# PZT_Board.net
KiCad netlist of a schematic drawn in Altium Designer
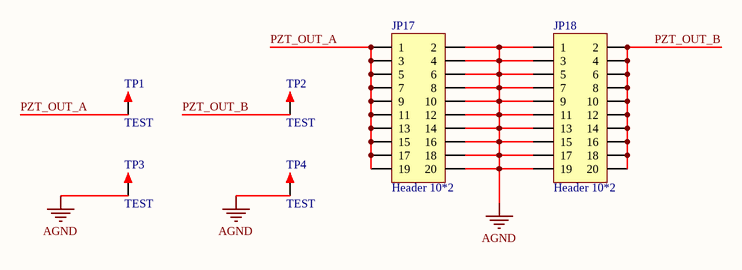
[diagram p0: PZT Board.SchDoc]

(export (version "E")
  (design (tool "Eeschema 10.0.6"))
  (components
    (comp (ref "JP17")
      (value "Header 10*2")
      (footprint "BTB-0.5MM-SMD-M_2*10PIN")
      (description "BTB Connector")
      (libsource (lib "4.6 - BTB连接器") (part "Header 10*2"))
    )
    (comp (ref "JP18")
      (value "Header 10*2")
      (footprint "BTB-0.5MM-SMD-M_2*10PIN")
      (description "BTB Connector")
      (libsource (lib "4.6 - BTB连接器") (part "Header 10*2"))
    )
    (comp (ref "TP1")
      (value "TEST")
      (footprint "TEST 2.0")
      (description "测试点")
      (fields (field (name "版权归属") "封装库来自淘宝 ID：黄晶宝石"))
      (libsource (lib "4.1 - 未分类器件") (part "TEST"))
    )
    (comp (ref "TP2")
      (value "TEST")
      (footprint "TEST 2.0")
      (description "测试点")
      (fields (field (name "版权归属") "封装库来自淘宝 ID：黄晶宝石"))
      (libsource (lib "4.1 - 未分类器件") (part "TEST"))
    )
    (comp (ref "TP3")
      (value "TEST")
      (footprint "TEST 2.0")
      (description "测试点")
      (fields (field (name "版权归属") "封装库来自淘宝 ID：黄晶宝石"))
      (libsource (lib "4.1 - 未分类器件") (part "TEST"))
    )
    (comp (ref "TP4")
      (value "TEST")
      (footprint "TEST 2.0")
      (description "测试点")
      (fields (field (name "版权归属") "封装库来自淘宝 ID：黄晶宝石"))
      (libsource (lib "4.1 - 未分类器件") (part "TEST"))
    )
  )
  (nets
    (net (code "1") (name "/PZT_OUT_A") (class "Default")
      (node (ref "JP17") (pin "1") (pinfunction "1_1") (pintype "passive"))
      (node (ref "JP17") (pin "11") (pinfunction "11_11") (pintype "passive"))
      (node (ref "JP17") (pin "13") (pinfunction "13_13") (pintype "passive"))
      (node (ref "JP17") (pin "15") (pinfunction "15_15") (pintype "passive"))
      (node (ref "JP17") (pin "17") (pinfunction "17_17") (pintype "passive"))
      (node (ref "JP17") (pin "19") (pinfunction "19_19") (pintype "passive"))
      (node (ref "JP17") (pin "3") (pinfunction "3_3") (pintype "passive"))
      (node (ref "JP17") (pin "5") (pinfunction "5_5") (pintype "passive"))
      (node (ref "JP17") (pin "7") (pinfunction "7_7") (pintype "passive"))
      (node (ref "JP17") (pin "9") (pinfunction "9_9") (pintype "passive"))
      (node (ref "TP1") (pin "1") (pinfunction "1_1") (pintype "passive"))
    )
    (net (code "2") (name "/PZT_OUT_B") (class "Default")
      (node (ref "JP18") (pin "10") (pinfunction "10_10") (pintype "passive"))
      (node (ref "JP18") (pin "12") (pinfunction "12_12") (pintype "passive"))
      (node (ref "JP18") (pin "14") (pinfunction "14_14") (pintype "passive"))
      (node (ref "JP18") (pin "16") (pinfunction "16_16") (pintype "passive"))
      (node (ref "JP18") (pin "18") (pinfunction "18_18") (pintype "passive"))
      (node (ref "JP18") (pin "2") (pinfunction "2_2") (pintype "passive"))
      (node (ref "JP18") (pin "20") (pinfunction "20_20") (pintype "passive"))
      (node (ref "JP18") (pin "4") (pinfunction "4_4") (pintype "passive"))
      (node (ref "JP18") (pin "6") (pinfunction "6_6") (pintype "passive"))
      (node (ref "JP18") (pin "8") (pinfunction "8_8") (pintype "passive"))
      (node (ref "TP2") (pin "1") (pinfunction "1_1") (pintype "passive"))
    )
    (net (code "3") (name "AGND") (class "Default")
      (node (ref "JP17") (pin "10") (pinfunction "10_10") (pintype "passive"))
      (node (ref "JP17") (pin "12") (pinfunction "12_12") (pintype "passive"))
      (node (ref "JP17") (pin "14") (pinfunction "14_14") (pintype "passive"))
      (node (ref "JP17") (pin "16") (pinfunction "16_16") (pintype "passive"))
      (node (ref "JP17") (pin "18") (pinfunction "18_18") (pintype "passive"))
      (node (ref "JP17") (pin "2") (pinfunction "2_2") (pintype "passive"))
      (node (ref "JP17") (pin "20") (pinfunction "20_20") (pintype "passive"))
      (node (ref "JP17") (pin "4") (pinfunction "4_4") (pintype "passive"))
      (node (ref "JP17") (pin "6") (pinfunction "6_6") (pintype "passive"))
      (node (ref "JP17") (pin "8") (pinfunction "8_8") (pintype "passive"))
      (node (ref "JP18") (pin "1") (pinfunction "1_1") (pintype "passive"))
      (node (ref "JP18") (pin "11") (pinfunction "11_11") (pintype "passive"))
      (node (ref "JP18") (pin "13") (pinfunction "13_13") (pintype "passive"))
      (node (ref "JP18") (pin "15") (pinfunction "15_15") (pintype "passive"))
      (node (ref "JP18") (pin "17") (pinfunction "17_17") (pintype "passive"))
      (node (ref "JP18") (pin "19") (pinfunction "19_19") (pintype "passive"))
      (node (ref "JP18") (pin "3") (pinfunction "3_3") (pintype "passive"))
      (node (ref "JP18") (pin "5") (pinfunction "5_5") (pintype "passive"))
      (node (ref "JP18") (pin "7") (pinfunction "7_7") (pintype "passive"))
      (node (ref "JP18") (pin "9") (pinfunction "9_9") (pintype "passive"))
      (node (ref "TP3") (pin "1") (pinfunction "1_1") (pintype "passive"))
      (node (ref "TP4") (pin "1") (pinfunction "1_1") (pintype "passive"))
    )
  )
)
